# TEMPLATE_Circuit.net
KiCad netlist of a schematic drawn in Altium Designer
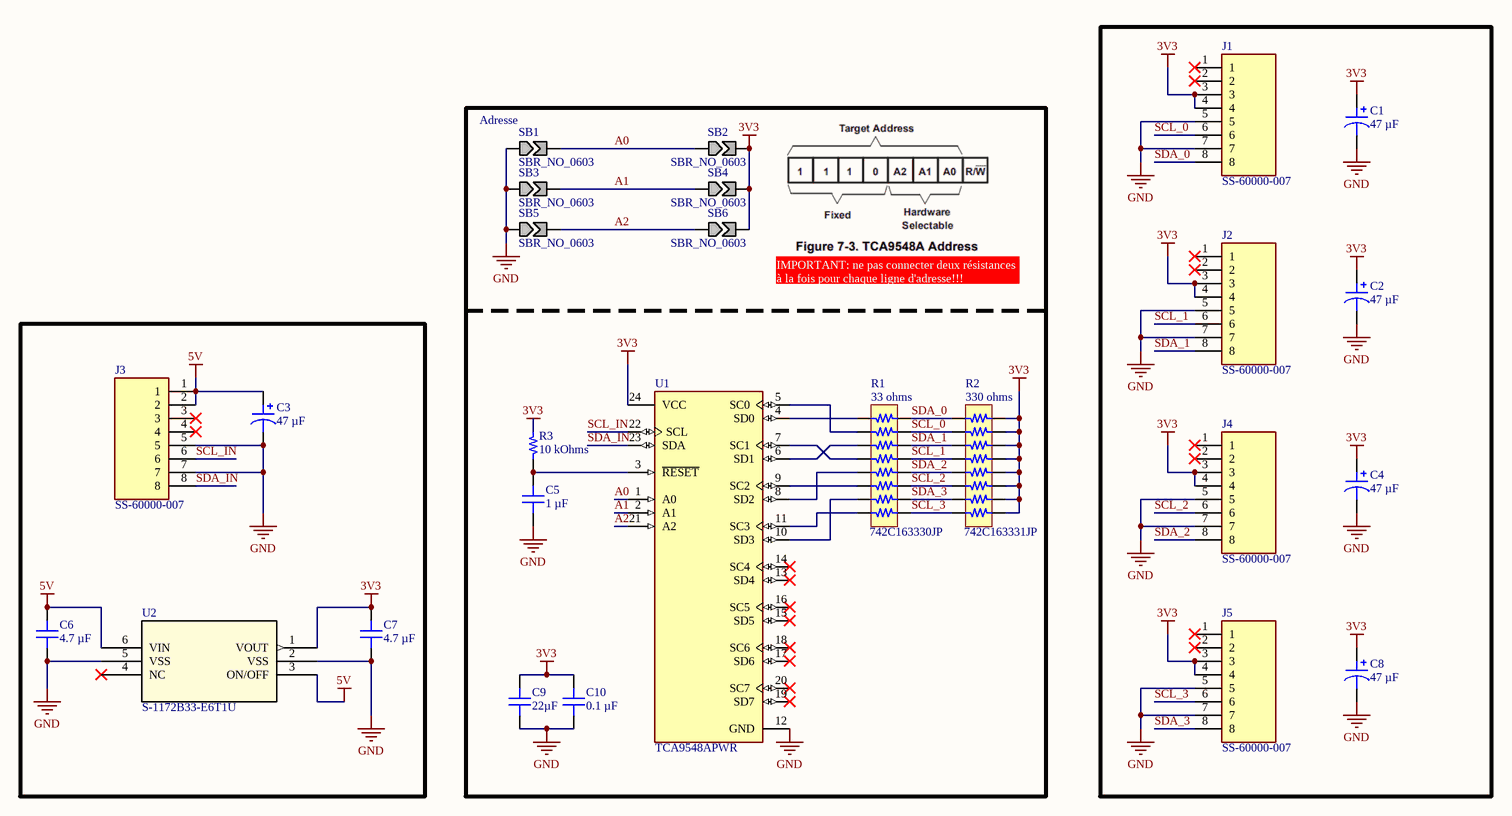
[diagram p0: TEMPLATE_Circuit.SchDoc]

(export (version "E")
  (design (tool "Eeschema 10.0.6"))
  (components
    (comp (ref "C1")
      (value "47 µF")
      (footprint "CAP ALSMD 6.6MM H6.1MM")
      (description "CAP ALUM 47UF 20% 35V SMD")
      (fields
        (field (name "PART NUMBER") "476SML035M")
        (field (name "MANUFACTURER") "Cornell Dubilier / Illinois Capacitor")
      )
      (libsource (lib "Celestial Altium Library - altium_library") (part "Polarised Capacitor"))
    )
    (comp (ref "C2")
      (value "47 µF")
      (footprint "CAP ALSMD 6.6MM H6.1MM")
      (description "CAP ALUM 47UF 20% 35V SMD")
      (fields
        (field (name "PART NUMBER") "476SML035M")
        (field (name "MANUFACTURER") "Cornell Dubilier / Illinois Capacitor")
      )
      (libsource (lib "Celestial Altium Library - altium_library") (part "Polarised Capacitor"))
    )
    (comp (ref "C3")
      (value "47 µF")
      (footprint "CAP ALSMD 6.6MM H6.1MM")
      (description "CAP ALUM 47UF 20% 35V SMD")
      (fields
        (field (name "PART NUMBER") "476SML035M")
        (field (name "MANUFACTURER") "Cornell Dubilier / Illinois Capacitor")
      )
      (libsource (lib "Celestial Altium Library - altium_library") (part "Polarised Capacitor"))
    )
    (comp (ref "C4")
      (value "47 µF")
      (footprint "CAP ALSMD 6.6MM H6.1MM")
      (description "CAP ALUM 47UF 20% 35V SMD")
      (fields
        (field (name "PART NUMBER") "476SML035M")
        (field (name "MANUFACTURER") "Cornell Dubilier / Illinois Capacitor")
      )
      (libsource (lib "Celestial Altium Library - altium_library") (part "Polarised Capacitor"))
    )
    (comp (ref "C5")
      (value "1 µF")
      (footprint "CAP 0603_1608")
      (description "CAP CER 1UF 16V X7R 0603")
      (fields (field (name "PART NUMBER") "C0603X105M4RACAUTO") (field (name "MANUFACTURER") "KEMET"))
      (libsource (lib "Celestial Altium Library - altium_library") (part "Capacitor"))
    )
    (comp (ref "C6")
      (value "4.7 µF")
      (footprint "CAP 0603_1608")
      (description "CAP CER 4.7UF 25V X5R 0603")
      (fields
        (field (name "PART NUMBER") "CL10A475KA8NQNC")
        (field (name "MANUFACTURER") "Samsung Electro-Mechanics")
      )
      (libsource (lib "Celestial Altium Library - altium_library") (part "Capacitor"))
    )
    (comp (ref "C7")
      (value "4.7 µF")
      (footprint "CAP 0603_1608")
      (description "CAP CER 4.7UF 25V X5R 0603")
      (fields
        (field (name "PART NUMBER") "CL10A475KA8NQNC")
        (field (name "MANUFACTURER") "Samsung Electro-Mechanics")
      )
      (libsource (lib "Celestial Altium Library - altium_library") (part "Capacitor"))
    )
    (comp (ref "C8")
      (value "47 µF")
      (footprint "CAP ALSMD 6.6MM H6.1MM")
      (description "CAP ALUM 47UF 20% 35V SMD")
      (fields
        (field (name "PART NUMBER") "476SML035M")
        (field (name "MANUFACTURER") "Cornell Dubilier / Illinois Capacitor")
      )
      (libsource (lib "Celestial Altium Library - altium_library") (part "Polarised Capacitor"))
    )
    (comp (ref "C9")
      (value "22µF")
      (footprint "CAP 0603_1608")
      (description "CAP CER 22UF 6.3V X5R 0603")
      (fields (field (name "PART NUMBER") "06036D226MAT2A") (field (name "MANUFACTURER") "AVX Corporation"))
      (libsource (lib "Celestial Altium Library - altium_library") (part "Capacitor"))
    )
    (comp (ref "C10")
      (value "0.1 µF")
      (footprint "CAP 0603_1608")
      (description "CAP CER 0.1UF 16V X7R 0603")
      (fields (field (name "PART NUMBER") "C0603C104M4RAC7411") (field (name "MANUFACTURER") "KEMET"))
      (libsource (lib "Celestial Altium Library - altium_library") (part "Capacitor"))
    )
    (comp (ref "J1")
      (value "SS-60000-007")
      (footprint "BEL_SS-60000-007")
      (description "Jack Modular Connector 8p8c _RJ45, Ethernet_ Vertical Unshielded Cat6")
      (fields (field (name "DIGI-KEY_PART_NUMBER") "380-1094-5-ND") (field (name "MF") "Stewart Connector"))
      (libsource (lib "SS-60000-007") (part "SS-60000-007"))
    )
    (comp (ref "J2")
      (value "SS-60000-007")
      (footprint "BEL_SS-60000-007")
      (description "Jack Modular Connector 8p8c _RJ45, Ethernet_ Vertical Unshielded Cat6")
      (fields (field (name "DIGI-KEY_PART_NUMBER") "380-1094-5-ND") (field (name "MF") "Stewart Connector"))
      (libsource (lib "SS-60000-007") (part "SS-60000-007"))
    )
    (comp (ref "J3")
      (value "SS-60000-007")
      (footprint "BEL_SS-60000-007")
      (description "Jack Modular Connector 8p8c _RJ45, Ethernet_ Vertical Unshielded Cat6")
      (fields (field (name "DIGI-KEY_PART_NUMBER") "380-1094-5-ND") (field (name "MF") "Stewart Connector"))
      (libsource (lib "") (part "SS-60000-007_1"))
    )
    (comp (ref "J4")
      (value "SS-60000-007")
      (footprint "BEL_SS-60000-007")
      (description "Jack Modular Connector 8p8c _RJ45, Ethernet_ Vertical Unshielded Cat6")
      (fields (field (name "DIGI-KEY_PART_NUMBER") "380-1094-5-ND") (field (name "MF") "Stewart Connector"))
      (libsource (lib "SS-60000-007") (part "SS-60000-007"))
    )
    (comp (ref "J5")
      (value "SS-60000-007")
      (footprint "BEL_SS-60000-007")
      (description "Jack Modular Connector 8p8c _RJ45, Ethernet_ Vertical Unshielded Cat6")
      (fields (field (name "DIGI-KEY_PART_NUMBER") "380-1094-5-ND") (field (name "MF") "Stewart Connector"))
      (libsource (lib "SS-60000-007") (part "SS-60000-007"))
    )
    (comp (ref "R1")
      (value "742C163330JP")
      (footprint "RESNET 2506-16 CONCAVE")
      (description "RES ARRAY 8 RES 33 OHM 2506")
      (fields (field (name "MANUFACTURER") "CTS Resistor Products") (field (name "TOLERANCE") "±5%"))
      (libsource (lib "Celestial Altium Library - altium_library") (part "Resistor Array (8 Circuit)"))
    )
    (comp (ref "R2")
      (value "742C163331JP")
      (footprint "RESNET 2506-16 CONCAVE")
      (description "RES ARRAY 8 RES 330 OHM 2506")
      (fields (field (name "MANUFACTURER") "CTS Resistor Products") (field (name "TOLERANCE") "±5%"))
      (libsource (lib "Celestial Altium Library - altium_library") (part "Resistor Array (8 Circuit)"))
    )
    (comp (ref "R3")
      (value "10 kOhms")
      (footprint "RES 0603_1608")
      (description "RES SMD 10K OHM 5% 1/4W 0603")
      (fields (field (name "PART NUMBER") "RCS060310K0JNEA") (field (name "MANUFACTURER") "Vishay Dale"))
      (libsource (lib "Celestial Altium Library - altium_library") (part "Resistor"))
    )
    (comp (ref "SB1")
      (value "SBR_NO_0603")
      (footprint "0603_solderBridge_NO")
      (description "Solder Bridge 0603 NO")
      (fields (field (name "SOURCE") "macro_keyboard_TEMP_LIB.SchLib"))
      (libsource (lib "Cegep de Sherbrooke") (part "SBR_NO_0603"))
    )
    (comp (ref "SB2")
      (value "SBR_NO_0603")
      (footprint "0603_solderBridge_NO")
      (description "Solder Bridge 0603 NO")
      (fields (field (name "SOURCE") "macro_keyboard_TEMP_LIB.SchLib"))
      (libsource (lib "Cegep de Sherbrooke") (part "SBR_NO_0603"))
    )
    (comp (ref "SB3")
      (value "SBR_NO_0603")
      (footprint "0603_solderBridge_NO")
      (description "Solder Bridge 0603 NO")
      (fields (field (name "SOURCE") "macro_keyboard_TEMP_LIB.SchLib"))
      (libsource (lib "Cegep de Sherbrooke") (part "SBR_NO_0603"))
    )
    (comp (ref "SB4")
      (value "SBR_NO_0603")
      (footprint "0603_solderBridge_NO")
      (description "Solder Bridge 0603 NO")
      (fields (field (name "SOURCE") "macro_keyboard_TEMP_LIB.SchLib"))
      (libsource (lib "Cegep de Sherbrooke") (part "SBR_NO_0603"))
    )
    (comp (ref "SB5")
      (value "SBR_NO_0603")
      (footprint "0603_solderBridge_NO")
      (description "Solder Bridge 0603 NO")
      (fields (field (name "SOURCE") "macro_keyboard_TEMP_LIB.SchLib"))
      (libsource (lib "Cegep de Sherbrooke") (part "SBR_NO_0603"))
    )
    (comp (ref "SB6")
      (value "SBR_NO_0603")
      (footprint "0603_solderBridge_NO")
      (description "Solder Bridge 0603 NO")
      (fields (field (name "SOURCE") "macro_keyboard_TEMP_LIB.SchLib"))
      (libsource (lib "Cegep de Sherbrooke") (part "SBR_NO_0603"))
    )
    (comp (ref "U1")
      (value "TCA9548APWR")
      (footprint "FP-PW0024A-MFG")
      (description "IC I2C SW 8CH W/RESET 24TSSOP")
      (fields
        (field (name "MANUFACTURER") "Texas Instruments")
        (field (name "OCTOPART") "https://octopart.com/tca9548apwr-texas+instruments-22266789")
      )
      (libsource (lib "Altium Content Vault") (part "aab65143522579f0e88a32f493a4230"))
    )
    (comp (ref "U2")
      (value "S-1172B33-E6T1U")
      (footprint "HSOP-6_FH006-A-P-SD-2.1_ABL")
      (description "No Description Available")
      (libsource (lib "S-1172B33-E6T1U") (part "S-1172B33-E6T1U"))
    )
  )
  (nets
    (net (code "1") (name "/A0") (class "Default")
      (node (ref "SB1") (pin "2") (pinfunction "2_2") (pintype "passive"))
      (node (ref "SB2") (pin "1") (pinfunction "1_1") (pintype "passive"))
      (node (ref "U1") (pin "1") (pinfunction "A0_1") (pintype "input"))
    )
    (net (code "2") (name "/A1") (class "Default")
      (node (ref "SB3") (pin "2") (pinfunction "2_2") (pintype "passive"))
      (node (ref "SB4") (pin "1") (pinfunction "1_1") (pintype "passive"))
      (node (ref "U1") (pin "2") (pinfunction "A1_2") (pintype "input"))
    )
    (net (code "3") (name "/A2") (class "Default")
      (node (ref "SB5") (pin "2") (pinfunction "2_2") (pintype "passive"))
      (node (ref "SB6") (pin "1") (pinfunction "1_1") (pintype "passive"))
      (node (ref "U1") (pin "21") (pinfunction "A2_21") (pintype "input"))
    )
    (net (code "4") (name "/SCL_0") (class "Default")
      (node (ref "J1") (pin "6") (pinfunction "6_6") (pintype "passive"))
      (node (ref "R1") (pin "2") (pinfunction "2_2") (pintype "passive"))
      (node (ref "R2") (pin "15") (pinfunction "15_15") (pintype "passive"))
    )
    (net (code "5") (name "/SCL_1") (class "Default")
      (node (ref "J2") (pin "6") (pinfunction "6_6") (pintype "passive"))
      (node (ref "R1") (pin "4") (pinfunction "4_4") (pintype "passive"))
      (node (ref "R2") (pin "13") (pinfunction "13_13") (pintype "passive"))
    )
    (net (code "6") (name "/SCL_2") (class "Default")
      (node (ref "J4") (pin "6") (pinfunction "6_6") (pintype "passive"))
      (node (ref "R1") (pin "6") (pinfunction "6_6") (pintype "passive"))
      (node (ref "R2") (pin "11") (pinfunction "11_11") (pintype "passive"))
    )
    (net (code "7") (name "/SCL_3") (class "Default")
      (node (ref "J5") (pin "6") (pinfunction "6_6") (pintype "passive"))
      (node (ref "R1") (pin "8") (pinfunction "8_8") (pintype "passive"))
      (node (ref "R2") (pin "9") (pinfunction "9_9") (pintype "passive"))
    )
    (net (code "8") (name "/SCL_IN") (class "Default")
      (node (ref "J3") (pin "6") (pinfunction "6_6") (pintype "passive"))
      (node (ref "U1") (pin "22") (pinfunction "SCL_22") (pintype "bidirectional"))
    )
    (net (code "9") (name "/SDA_0") (class "Default")
      (node (ref "J1") (pin "8") (pinfunction "8_8") (pintype "passive"))
      (node (ref "R1") (pin "1") (pinfunction "1_1") (pintype "passive"))
      (node (ref "R2") (pin "16") (pinfunction "16_16") (pintype "passive"))
    )
    (net (code "10") (name "/SDA_1") (class "Default")
      (node (ref "J2") (pin "8") (pinfunction "8_8") (pintype "passive"))
      (node (ref "R1") (pin "3") (pinfunction "3_3") (pintype "passive"))
      (node (ref "R2") (pin "14") (pinfunction "14_14") (pintype "passive"))
    )
    (net (code "11") (name "/SDA_2") (class "Default")
      (node (ref "J4") (pin "8") (pinfunction "8_8") (pintype "passive"))
      (node (ref "R1") (pin "5") (pinfunction "6_5") (pintype "passive"))
      (node (ref "R2") (pin "12") (pinfunction "12_12") (pintype "passive"))
    )
    (net (code "12") (name "/SDA_3") (class "Default")
      (node (ref "J5") (pin "8") (pinfunction "8_8") (pintype "passive"))
      (node (ref "R1") (pin "7") (pinfunction "7_7") (pintype "passive"))
      (node (ref "R2") (pin "10") (pinfunction "10_10") (pintype "passive"))
    )
    (net (code "13") (name "/SDA_IN") (class "Default")
      (node (ref "J3") (pin "8") (pinfunction "8_8") (pintype "passive"))
      (node (ref "U1") (pin "23") (pinfunction "SDA_23") (pintype "bidirectional"))
    )
    (net (code "14") (name "3V3") (class "Default")
      (node (ref "C1") (pin "1") (pinfunction "1_1") (pintype "passive"))
      (node (ref "C10") (pin "2") (pinfunction "2_2") (pintype "passive"))
      (node (ref "C2") (pin "1") (pinfunction "1_1") (pintype "passive"))
      (node (ref "C4") (pin "1") (pinfunction "1_1") (pintype "passive"))
      (node (ref "C7") (pin "2") (pinfunction "2_2") (pintype "passive"))
      (node (ref "C8") (pin "1") (pinfunction "1_1") (pintype "passive"))
      (node (ref "C9") (pin "2") (pinfunction "2_2") (pintype "passive"))
      (node (ref "J1") (pin "3") (pinfunction "3_3") (pintype "passive"))
      (node (ref "J1") (pin "4") (pinfunction "4_4") (pintype "passive"))
      (node (ref "J2") (pin "3") (pinfunction "3_3") (pintype "passive"))
      (node (ref "J2") (pin "4") (pinfunction "4_4") (pintype "passive"))
      (node (ref "J4") (pin "3") (pinfunction "3_3") (pintype "passive"))
      (node (ref "J4") (pin "4") (pinfunction "4_4") (pintype "passive"))
      (node (ref "J5") (pin "3") (pinfunction "3_3") (pintype "passive"))
      (node (ref "J5") (pin "4") (pinfunction "4_4") (pintype "passive"))
      (node (ref "R2") (pin "1") (pinfunction "1_1") (pintype "passive"))
      (node (ref "R2") (pin "2") (pinfunction "2_2") (pintype "passive"))
      (node (ref "R2") (pin "3") (pinfunction "3_3") (pintype "passive"))
      (node (ref "R2") (pin "4") (pinfunction "4_4") (pintype "passive"))
      (node (ref "R2") (pin "5") (pinfunction "6_5") (pintype "passive"))
      (node (ref "R2") (pin "6") (pinfunction "6_6") (pintype "passive"))
      (node (ref "R2") (pin "7") (pinfunction "7_7") (pintype "passive"))
      (node (ref "R2") (pin "8") (pinfunction "8_8") (pintype "passive"))
      (node (ref "R3") (pin "2") (pinfunction "2_2") (pintype "passive"))
      (node (ref "SB2") (pin "2") (pinfunction "2_2") (pintype "passive"))
      (node (ref "SB4") (pin "2") (pinfunction "2_2") (pintype "passive"))
      (node (ref "SB6") (pin "2") (pinfunction "2_2") (pintype "passive"))
      (node (ref "U1") (pin "24") (pinfunction "VCC_24") (pintype "power_in"))
      (node (ref "U2") (pin "1") (pinfunction "VOUT_1") (pintype "output"))
    )
    (net (code "15") (name "5V") (class "Default")
      (node (ref "C3") (pin "1") (pinfunction "1_1") (pintype "passive"))
      (node (ref "C6") (pin "2") (pinfunction "2_2") (pintype "passive"))
      (node (ref "J3") (pin "1") (pinfunction "1_1") (pintype "passive"))
      (node (ref "J3") (pin "2") (pinfunction "2_2") (pintype "passive"))
      (node (ref "U2") (pin "3") (pinfunction "ON/OFF_3") (pintype "passive"))
      (node (ref "U2") (pin "6") (pinfunction "VIN_6") (pintype "power_in"))
    )
    (net (code "16") (name "GND") (class "Default")
      (node (ref "C1") (pin "2") (pinfunction "2_2") (pintype "passive"))
      (node (ref "C10") (pin "1") (pinfunction "1_1") (pintype "passive"))
      (node (ref "C2") (pin "2") (pinfunction "2_2") (pintype "passive"))
      (node (ref "C3") (pin "2") (pinfunction "2_2") (pintype "passive"))
      (node (ref "C4") (pin "2") (pinfunction "2_2") (pintype "passive"))
      (node (ref "C5") (pin "1") (pinfunction "1_1") (pintype "passive"))
      (node (ref "C6") (pin "1") (pinfunction "1_1") (pintype "passive"))
      (node (ref "C7") (pin "1") (pinfunction "1_1") (pintype "passive"))
      (node (ref "C8") (pin "2") (pinfunction "2_2") (pintype "passive"))
      (node (ref "C9") (pin "1") (pinfunction "1_1") (pintype "passive"))
      (node (ref "J1") (pin "5") (pinfunction "5_5") (pintype "passive"))
      (node (ref "J1") (pin "7") (pinfunction "7_7") (pintype "passive"))
      (node (ref "J2") (pin "5") (pinfunction "5_5") (pintype "passive"))
      (node (ref "J2") (pin "7") (pinfunction "7_7") (pintype "passive"))
      (node (ref "J3") (pin "5") (pinfunction "5_5") (pintype "passive"))
      (node (ref "J3") (pin "7") (pinfunction "7_7") (pintype "passive"))
      (node (ref "J4") (pin "5") (pinfunction "5_5") (pintype "passive"))
      (node (ref "J4") (pin "7") (pinfunction "7_7") (pintype "passive"))
      (node (ref "J5") (pin "5") (pinfunction "5_5") (pintype "passive"))
      (node (ref "J5") (pin "7") (pinfunction "7_7") (pintype "passive"))
      (node (ref "SB1") (pin "1") (pinfunction "1_1") (pintype "passive"))
      (node (ref "SB3") (pin "1") (pinfunction "1_1") (pintype "passive"))
      (node (ref "SB5") (pin "1") (pinfunction "1_1") (pintype "passive"))
      (node (ref "U1") (pin "12") (pinfunction "GND_12") (pintype "power_in"))
      (node (ref "U2") (pin "2") (pinfunction "VSS_2") (pintype "power_in"))
      (node (ref "U2") (pin "5") (pinfunction "VSS_5") (pintype "power_in"))
    )
    (net (code "17") (name "Net-(U1-SC0)") (class "Default")
      (node (ref "R1") (pin "15") (pinfunction "15_15") (pintype "passive"))
      (node (ref "U1") (pin "5") (pinfunction "SC0_5") (pintype "bidirectional"))
    )
    (net (code "18") (name "Net-(U1-SC1)") (class "Default")
      (node (ref "R1") (pin "13") (pinfunction "13_13") (pintype "passive"))
      (node (ref "U1") (pin "7") (pinfunction "SC1_7") (pintype "bidirectional"))
    )
    (net (code "19") (name "Net-(U1-SC2)") (class "Default")
      (node (ref "R1") (pin "11") (pinfunction "11_11") (pintype "passive"))
      (node (ref "U1") (pin "9") (pinfunction "SC2_9") (pintype "bidirectional"))
    )
    (net (code "20") (name "Net-(U1-SC3)") (class "Default")
      (node (ref "R1") (pin "9") (pinfunction "9_9") (pintype "passive"))
      (node (ref "U1") (pin "11") (pinfunction "SC3_11") (pintype "bidirectional"))
    )
    (net (code "21") (name "Net-(U1-SD0)") (class "Default")
      (node (ref "R1") (pin "16") (pinfunction "16_16") (pintype "passive"))
      (node (ref "U1") (pin "4") (pinfunction "SD0_4") (pintype "bidirectional"))
    )
    (net (code "22") (name "Net-(U1-SD1)") (class "Default")
      (node (ref "R1") (pin "14") (pinfunction "14_14") (pintype "passive"))
      (node (ref "U1") (pin "6") (pinfunction "SD1_6") (pintype "bidirectional"))
    )
    (net (code "23") (name "Net-(U1-SD2)") (class "Default")
      (node (ref "R1") (pin "12") (pinfunction "12_12") (pintype "passive"))
      (node (ref "U1") (pin "8") (pinfunction "SD2_8") (pintype "bidirectional"))
    )
    (net (code "24") (name "Net-(U1-SD3)") (class "Default")
      (node (ref "R1") (pin "10") (pinfunction "10_10") (pintype "passive"))
      (node (ref "U1") (pin "10") (pinfunction "SD3_10") (pintype "bidirectional"))
    )
    (net (code "25") (name "Net-(U1-~{RESET})") (class "Default")
      (node (ref "C5") (pin "2") (pinfunction "2_2") (pintype "passive"))
      (node (ref "R3") (pin "1") (pinfunction "1_1") (pintype "passive"))
      (node (ref "U1") (pin "3") (pinfunction "~{RESET}_3") (pintype "input"))
    )
    (net (code "26") (name "unconnected-(J1-Pad1)") (class "Default")
      (node (ref "J1") (pin "1") (pinfunction "1_1") (pintype "passive+no_connect"))
    )
    (net (code "27") (name "unconnected-(J1-Pad2)") (class "Default")
      (node (ref "J1") (pin "2") (pinfunction "2_2") (pintype "passive+no_connect"))
    )
    (net (code "28") (name "unconnected-(J2-Pad1)") (class "Default")
      (node (ref "J2") (pin "1") (pinfunction "1_1") (pintype "passive+no_connect"))
    )
    (net (code "29") (name "unconnected-(J2-Pad2)") (class "Default")
      (node (ref "J2") (pin "2") (pinfunction "2_2") (pintype "passive+no_connect"))
    )
    (net (code "30") (name "unconnected-(J3-Pad3)") (class "Default")
      (node (ref "J3") (pin "3") (pinfunction "3_3") (pintype "passive+no_connect"))
    )
    (net (code "31") (name "unconnected-(J3-Pad4)") (class "Default")
      (node (ref "J3") (pin "4") (pinfunction "4_4") (pintype "passive+no_connect"))
    )
    (net (code "32") (name "unconnected-(J4-Pad1)") (class "Default")
      (node (ref "J4") (pin "1") (pinfunction "1_1") (pintype "passive+no_connect"))
    )
    (net (code "33") (name "unconnected-(J4-Pad2)") (class "Default")
      (node (ref "J4") (pin "2") (pinfunction "2_2") (pintype "passive+no_connect"))
    )
    (net (code "34") (name "unconnected-(J5-Pad1)") (class "Default")
      (node (ref "J5") (pin "1") (pinfunction "1_1") (pintype "passive+no_connect"))
    )
    (net (code "35") (name "unconnected-(J5-Pad2)") (class "Default")
      (node (ref "J5") (pin "2") (pinfunction "2_2") (pintype "passive+no_connect"))
    )
    (net (code "36") (name "unconnected-(U1-SC4-Pad14)") (class "Default")
      (node (ref "U1") (pin "14") (pinfunction "SC4_14") (pintype "bidirectional+no_connect"))
    )
    (net (code "37") (name "unconnected-(U1-SC5-Pad16)") (class "Default")
      (node (ref "U1") (pin "16") (pinfunction "SC5_16") (pintype "bidirectional+no_connect"))
    )
    (net (code "38") (name "unconnected-(U1-SC6-Pad18)") (class "Default")
      (node (ref "U1") (pin "18") (pinfunction "SC6_18") (pintype "bidirectional+no_connect"))
    )
    (net (code "39") (name "unconnected-(U1-SC7-Pad20)") (class "Default")
      (node (ref "U1") (pin "20") (pinfunction "SC7_20") (pintype "bidirectional+no_connect"))
    )
    (net (code "40") (name "unconnected-(U1-SD4-Pad13)") (class "Default")
      (node (ref "U1") (pin "13") (pinfunction "SD4_13") (pintype "bidirectional+no_connect"))
    )
    (net (code "41") (name "unconnected-(U1-SD5-Pad15)") (class "Default")
      (node (ref "U1") (pin "15") (pinfunction "SD5_15") (pintype "bidirectional+no_connect"))
    )
    (net (code "42") (name "unconnected-(U1-SD6-Pad17)") (class "Default")
      (node (ref "U1") (pin "17") (pinfunction "SD6_17") (pintype "bidirectional+no_connect"))
    )
    (net (code "43") (name "unconnected-(U1-SD7-Pad19)") (class "Default")
      (node (ref "U1") (pin "19") (pinfunction "SD7_19") (pintype "bidirectional+no_connect"))
    )
    (net (code "44") (name "unconnected-(U2-NC-Pad4)") (class "Default")
      (node (ref "U2") (pin "4") (pinfunction "NC_4") (pintype "passive+no_connect"))
    )
  )
)
